# led_ppm_display.net
KiCad netlist of a schematic drawn in EAGLE
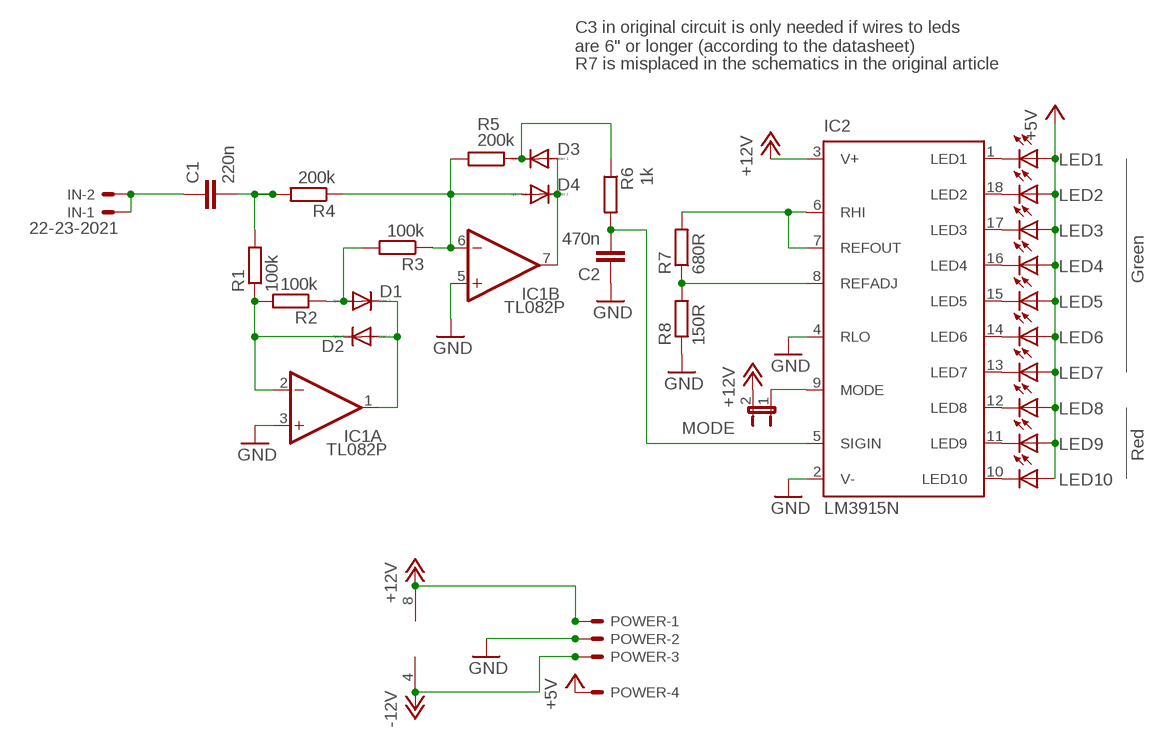
[diagram p0: schematic, sheet 1]

(export (version "E")
  (design (tool "Eeschema 10.0.6"))
  (components
    (comp (ref "C1")
      (value "220n")
      (footprint "eagle-import:C050-025X075")
      (libsource (lib "eagle-import") (part "C-EU050-025X075"))
    )
    (comp (ref "C2")
      (value "470n")
      (footprint "eagle-import:C050-025X075")
      (libsource (lib "eagle-import") (part "C-EU050-025X075"))
    )
    (comp (ref "D1")
      (value "1N4148DOJ35-5")
      (footprint "eagle-import:DO35-5J")
      (libsource (lib "eagle-import") (part "1N4148DOJ35-5"))
    )
    (comp (ref "D2")
      (value "1N4148DOJ35-5")
      (footprint "eagle-import:DO35-5J")
      (libsource (lib "eagle-import") (part "1N4148DOJ35-5"))
    )
    (comp (ref "D3")
      (value "1N4148DOJ35-5")
      (footprint "eagle-import:DO35-5J")
      (libsource (lib "eagle-import") (part "1N4148DOJ35-5"))
    )
    (comp (ref "D4")
      (value "1N4148DOJ35-5")
      (footprint "eagle-import:DO35-5J")
      (libsource (lib "eagle-import") (part "1N4148DOJ35-5"))
    )
    (comp (ref "IC1")
      (value "TL082P")
      (footprint "eagle-import:DIL08")
      (libsource (lib "eagle-import") (part "TL082P"))
    )
    (comp (ref "IC2")
      (value "LM3915N")
      (footprint "eagle-import:DIL18")
      (libsource (lib "eagle-import") (part "LM391N5"))
    )
    (comp (ref "IN")
      (value "22-23-2021")
      (footprint "eagle-import:22-23-2021")
      (fields (field (name "MF") "MOLEX"))
      (libsource (lib "eagle-import") (part "22-23-2021"))
    )
    (comp (ref "LED1")
      (value "LED3MM")
      (footprint "eagle-import:LED3MM")
      (libsource (lib "eagle-import") (part "LED3MM"))
    )
    (comp (ref "LED2")
      (value "LED3MM")
      (footprint "eagle-import:LED3MM")
      (libsource (lib "eagle-import") (part "LED3MM"))
    )
    (comp (ref "LED3")
      (value "LED3MM")
      (footprint "eagle-import:LED3MM")
      (libsource (lib "eagle-import") (part "LED3MM"))
    )
    (comp (ref "LED4")
      (value "LED3MM")
      (footprint "eagle-import:LED3MM")
      (libsource (lib "eagle-import") (part "LED3MM"))
    )
    (comp (ref "LED5")
      (value "LED3MM")
      (footprint "eagle-import:LED3MM")
      (libsource (lib "eagle-import") (part "LED3MM"))
    )
    (comp (ref "LED6")
      (value "LED3MM")
      (footprint "eagle-import:LED3MM")
      (libsource (lib "eagle-import") (part "LED3MM"))
    )
    (comp (ref "LED7")
      (value "LED3MM")
      (footprint "eagle-import:LED3MM")
      (libsource (lib "eagle-import") (part "LED3MM"))
    )
    (comp (ref "LED8")
      (value "LED3MM")
      (footprint "eagle-import:LED3MM")
      (libsource (lib "eagle-import") (part "LED3MM"))
    )
    (comp (ref "LED9")
      (value "LED3MM")
      (footprint "eagle-import:LED3MM")
      (libsource (lib "eagle-import") (part "LED3MM"))
    )
    (comp (ref "LED10")
      (value "LED3MM")
      (footprint "eagle-import:LED3MM")
      (libsource (lib "eagle-import") (part "LED3MM"))
    )
    (comp (ref "MODE")
      (value "JP1E")
      (footprint "eagle-import:JP1")
      (libsource (lib "eagle-import") (part "JP1E"))
    )
    (comp (ref "POWER")
      (value "KK-156-4")
      (footprint "eagle-import:KK-156-4")
      (libsource (lib "eagle-import") (part "KK-156-4"))
    )
    (comp (ref "R1")
      (value "100k")
      (footprint "eagle-import:0207_7")
      (libsource (lib "eagle-import") (part "R-EU_0207/7"))
    )
    (comp (ref "R2")
      (value "100k")
      (footprint "eagle-import:0207_7")
      (libsource (lib "eagle-import") (part "R-EU_0207/7"))
    )
    (comp (ref "R3")
      (value "100k")
      (footprint "eagle-import:0207_7")
      (libsource (lib "eagle-import") (part "R-EU_0207/7"))
    )
    (comp (ref "R4")
      (value "200k")
      (footprint "eagle-import:0207_7")
      (libsource (lib "eagle-import") (part "R-EU_0207/7"))
    )
    (comp (ref "R5")
      (value "200k")
      (footprint "eagle-import:0207_7")
      (libsource (lib "eagle-import") (part "R-EU_0207/7"))
    )
    (comp (ref "R6")
      (value "1k")
      (footprint "eagle-import:0207_7")
      (libsource (lib "eagle-import") (part "R-EU_0207/7"))
    )
    (comp (ref "R7")
      (value "680R")
      (footprint "eagle-import:0207_7")
      (libsource (lib "eagle-import") (part "R-EU_0207/7"))
    )
    (comp (ref "R8")
      (value "150R")
      (footprint "eagle-import:0207_7")
      (libsource (lib "eagle-import") (part "R-EU_0207/7"))
    )
  )
  (nets
    (net (code "1") (name "+5V") (class "Default")
      (node (ref "LED1") (pin "A") (pinfunction "A_A") (pintype "passive"))
      (node (ref "LED10") (pin "A") (pinfunction "A_A") (pintype "passive"))
      (node (ref "LED2") (pin "A") (pinfunction "A_A") (pintype "passive"))
      (node (ref "LED3") (pin "A") (pinfunction "A_A") (pintype "passive"))
      (node (ref "LED4") (pin "A") (pinfunction "A_A") (pintype "passive"))
      (node (ref "LED5") (pin "A") (pinfunction "A_A") (pintype "passive"))
      (node (ref "LED6") (pin "A") (pinfunction "A_A") (pintype "passive"))
      (node (ref "LED7") (pin "A") (pinfunction "A_A") (pintype "passive"))
      (node (ref "LED8") (pin "A") (pinfunction "A_A") (pintype "passive"))
      (node (ref "LED9") (pin "A") (pinfunction "A_A") (pintype "passive"))
      (node (ref "POWER") (pin "4") (pinfunction "S_4") (pintype "passive"))
    )
    (net (code "2") (name "+12V") (class "Default")
      (node (ref "IC1") (pin "8") (pinfunction "V+_8") (pintype "power_in"))
      (node (ref "IC2") (pin "3") (pinfunction "V+_3") (pintype "power_in"))
      (node (ref "MODE") (pin "2") (pinfunction "2_2") (pintype "passive"))
      (node (ref "POWER") (pin "1") (pinfunction "S_1") (pintype "passive"))
    )
    (net (code "3") (name "-12V") (class "Default")
      (node (ref "IC1") (pin "4") (pinfunction "V-_4") (pintype "power_in"))
      (node (ref "POWER") (pin "3") (pinfunction "S_3") (pintype "passive"))
    )
    (net (code "4") (name "GND") (class "Default")
      (node (ref "C2") (pin "1") (pinfunction "1_1") (pintype "passive"))
      (node (ref "IC1") (pin "3") (pinfunction "+IN_3") (pintype "input"))
      (node (ref "IC1") (pin "5") (pinfunction "+IN_5") (pintype "input"))
      (node (ref "IC2") (pin "2") (pinfunction "V-_2") (pintype "power_in"))
      (node (ref "IC2") (pin "4") (pinfunction "RLO_4") (pintype "input"))
      (node (ref "POWER") (pin "2") (pinfunction "S_2") (pintype "passive"))
      (node (ref "R8") (pin "1") (pinfunction "1_1") (pintype "passive"))
    )
    (net (code "5") (name "Net-(C1-Pad2)") (class "Default")
      (node (ref "C1") (pin "2") (pinfunction "2_2") (pintype "passive"))
      (node (ref "R1") (pin "2") (pinfunction "2_2") (pintype "passive"))
      (node (ref "R4") (pin "2") (pinfunction "2_2") (pintype "passive"))
    )
    (net (code "6") (name "Net-(D1-PadA)") (class "Default")
      (node (ref "D1") (pin "A") (pinfunction "A_A") (pintype "passive"))
      (node (ref "R2") (pin "1") (pinfunction "1_1") (pintype "passive"))
      (node (ref "R3") (pin "2") (pinfunction "2_2") (pintype "passive"))
    )
    (net (code "7") (name "Net-(D3-PadC)") (class "Default")
      (node (ref "D3") (pin "C") (pinfunction "C_C") (pintype "passive"))
      (node (ref "R5") (pin "1") (pinfunction "1_1") (pintype "passive"))
      (node (ref "R6") (pin "1") (pinfunction "1_1") (pintype "passive"))
    )
    (net (code "8") (name "Net-(IC1A--IN)") (class "Default")
      (node (ref "D2") (pin "C") (pinfunction "C_C") (pintype "passive"))
      (node (ref "IC1") (pin "2") (pinfunction "-IN_2") (pintype "input"))
      (node (ref "R1") (pin "1") (pinfunction "1_1") (pintype "passive"))
      (node (ref "R2") (pin "2") (pinfunction "2_2") (pintype "passive"))
    )
    (net (code "9") (name "Net-(IC1A-OUT)") (class "Default")
      (node (ref "D1") (pin "C") (pinfunction "C_C") (pintype "passive"))
      (node (ref "D2") (pin "A") (pinfunction "A_A") (pintype "passive"))
      (node (ref "IC1") (pin "1") (pinfunction "OUT_1") (pintype "output"))
    )
    (net (code "10") (name "Net-(IC1B--IN)") (class "Default")
      (node (ref "D4") (pin "A") (pinfunction "A_A") (pintype "passive"))
      (node (ref "IC1") (pin "6") (pinfunction "-IN_6") (pintype "input"))
      (node (ref "R3") (pin "1") (pinfunction "1_1") (pintype "passive"))
      (node (ref "R4") (pin "1") (pinfunction "1_1") (pintype "passive"))
      (node (ref "R5") (pin "2") (pinfunction "2_2") (pintype "passive"))
    )
    (net (code "11") (name "Net-(IC1B-OUT)") (class "Default")
      (node (ref "D3") (pin "A") (pinfunction "A_A") (pintype "passive"))
      (node (ref "D4") (pin "C") (pinfunction "C_C") (pintype "passive"))
      (node (ref "IC1") (pin "7") (pinfunction "OUT_7") (pintype "output"))
    )
    (net (code "12") (name "Net-(IC2-LED1)") (class "Default")
      (node (ref "IC2") (pin "1") (pinfunction "LED1_1") (pintype "output"))
      (node (ref "LED1") (pin "K") (pinfunction "C_K") (pintype "passive"))
    )
    (net (code "13") (name "Net-(IC2-LED2)") (class "Default")
      (node (ref "IC2") (pin "18") (pinfunction "LED2_18") (pintype "output"))
      (node (ref "LED2") (pin "K") (pinfunction "C_K") (pintype "passive"))
    )
    (net (code "14") (name "Net-(IC2-LED3)") (class "Default")
      (node (ref "IC2") (pin "17") (pinfunction "LED3_17") (pintype "output"))
      (node (ref "LED3") (pin "K") (pinfunction "C_K") (pintype "passive"))
    )
    (net (code "15") (name "Net-(IC2-LED4)") (class "Default")
      (node (ref "IC2") (pin "16") (pinfunction "LED4_16") (pintype "output"))
      (node (ref "LED4") (pin "K") (pinfunction "C_K") (pintype "passive"))
    )
    (net (code "16") (name "Net-(IC2-LED5)") (class "Default")
      (node (ref "IC2") (pin "15") (pinfunction "LED5_15") (pintype "output"))
      (node (ref "LED5") (pin "K") (pinfunction "C_K") (pintype "passive"))
    )
    (net (code "17") (name "Net-(IC2-LED6)") (class "Default")
      (node (ref "IC2") (pin "14") (pinfunction "LED6_14") (pintype "output"))
      (node (ref "LED6") (pin "K") (pinfunction "C_K") (pintype "passive"))
    )
    (net (code "18") (name "Net-(IC2-LED7)") (class "Default")
      (node (ref "IC2") (pin "13") (pinfunction "LED7_13") (pintype "output"))
      (node (ref "LED7") (pin "K") (pinfunction "C_K") (pintype "passive"))
    )
    (net (code "19") (name "Net-(IC2-LED8)") (class "Default")
      (node (ref "IC2") (pin "12") (pinfunction "LED8_12") (pintype "output"))
      (node (ref "LED8") (pin "K") (pinfunction "C_K") (pintype "passive"))
    )
    (net (code "20") (name "Net-(IC2-LED9)") (class "Default")
      (node (ref "IC2") (pin "11") (pinfunction "LED9_11") (pintype "output"))
      (node (ref "LED9") (pin "K") (pinfunction "C_K") (pintype "passive"))
    )
    (net (code "21") (name "Net-(IC2-LED10)") (class "Default")
      (node (ref "IC2") (pin "10") (pinfunction "LED10_10") (pintype "output"))
      (node (ref "LED10") (pin "K") (pinfunction "C_K") (pintype "passive"))
    )
    (net (code "22") (name "Net-(IC2-MODE)") (class "Default")
      (node (ref "IC2") (pin "9") (pinfunction "MODE_9") (pintype "input"))
      (node (ref "MODE") (pin "1") (pinfunction "1_1") (pintype "passive"))
    )
    (net (code "23") (name "Net-(IC2-REFADJ)") (class "Default")
      (node (ref "IC2") (pin "8") (pinfunction "REFADJ_8") (pintype "passive"))
      (node (ref "R7") (pin "1") (pinfunction "1_1") (pintype "passive"))
      (node (ref "R8") (pin "2") (pinfunction "2_2") (pintype "passive"))
    )
    (net (code "24") (name "Net-(IC2-REFOUT)") (class "Default")
      (node (ref "IC2") (pin "6") (pinfunction "RHI_6") (pintype "input"))
      (node (ref "IC2") (pin "7") (pinfunction "REFOUT_7") (pintype "output"))
      (node (ref "R7") (pin "2") (pinfunction "2_2") (pintype "passive"))
    )
    (net (code "25") (name "Net-(IC2-SIGIN)") (class "Default")
      (node (ref "C2") (pin "2") (pinfunction "2_2") (pintype "passive"))
      (node (ref "IC2") (pin "5") (pinfunction "SIGIN_5") (pintype "input"))
      (node (ref "R6") (pin "2") (pinfunction "2_2") (pintype "passive"))
    )
    (net (code "26") (name "Net-(INA-S)") (class "Default")
      (node (ref "C1") (pin "1") (pinfunction "1_1") (pintype "passive"))
      (node (ref "IN") (pin "1") (pinfunction "S_1") (pintype "passive"))
      (node (ref "IN") (pin "2") (pinfunction "S_2") (pintype "passive"))
    )
  )
)
